# Current_Scaler.net
KiCad netlist of a schematic drawn in Altium Designer
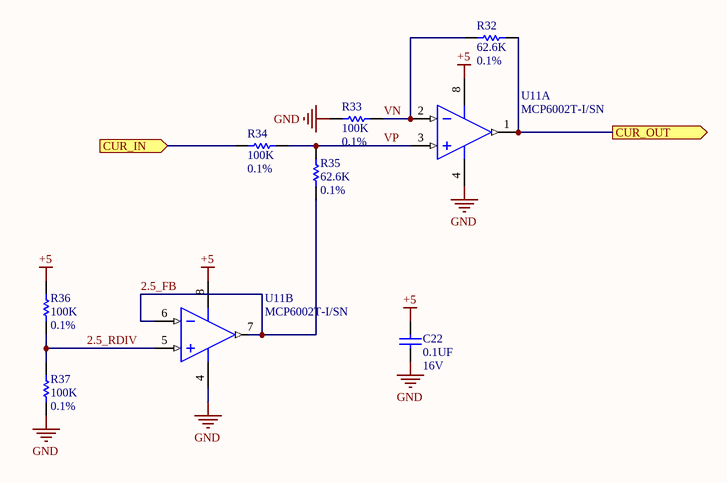
[diagram p0: Current Scaler.SchDoc]

(export (version "E")
  (design (tool "Eeschema 10.0.6"))
  (components
    (comp (ref "C22")
      (value "CAP 0603 0.1UF 16V 10% X7R")
      (footprint "0603_CAP")
      (description "Capacitor Surface Mount 0603 Footprint 0.1UF 16V 10% Tolerance Ceramic X7R")
      (fields
        (field (name "VAL") "0.1UF")
        (field (name "VOL") "16V")
        (field (name "MANUFACTURER") "Various")
        (field (name "VOLTAGE") "16V")
      )
      (libsource (lib "Passive Components") (part "cap"))
    )
    (comp (ref "R32")
      (value "RES 0603 62.6K 0.1%")
      (footprint "0603_RES")
      (description "Resistor Surface Mount, 51K Ohms, 0603 Footprint, 0.05% Tolerance 0.1W")
      (fields
        (field (name "VAL") "62.6K")
        (field (name "TOL") "0.1%")
        (field (name "MANUFACTURER") "Various")
        (field (name "TOLERANCE") "0.1%")
      )
      (libsource (lib "Passive Components") (part "res"))
    )
    (comp (ref "R33")
      (value "RES 0603 100K 0.1%")
      (footprint "0603_RES")
      (description "Resistor Surface Mount, 100K Ohms, 0603 Footprint, 0.1% Tolerance 0.1W")
      (fields
        (field (name "VAL") "100K")
        (field (name "TOL") "0.1%")
        (field (name "MANUFACTURER") "Various")
        (field (name "TOLERANCE") "0.1%")
      )
      (libsource (lib "Passive Components") (part "res"))
    )
    (comp (ref "R34")
      (value "RES 0603 100K 0.1%")
      (footprint "0603_RES")
      (description "Resistor Surface Mount, 100K Ohms, 0603 Footprint, 0.1% Tolerance 0.1W")
      (fields
        (field (name "VAL") "100K")
        (field (name "TOL") "0.1%")
        (field (name "MANUFACTURER") "Various")
        (field (name "TOLERANCE") "0.1%")
      )
      (libsource (lib "Passive Components") (part "res"))
    )
    (comp (ref "R35")
      (value "RES 0603 62.6K 0.1%")
      (footprint "0603_RES")
      (description "Resistor Surface Mount, 51K Ohms, 0603 Footprint, 0.05% Tolerance 0.1W")
      (fields
        (field (name "VAL") "62.6K")
        (field (name "TOL") "0.1%")
        (field (name "MANUFACTURER") "Various")
        (field (name "TOLERANCE") "0.1%")
      )
      (libsource (lib "Passive Components") (part "res"))
    )
    (comp (ref "R36")
      (value "RES 0603 100K 0.1%")
      (footprint "0603_RES")
      (description "Resistor Surface Mount, 100K Ohms, 0603 Footprint, 0.1% Tolerance 0.1W")
      (fields
        (field (name "VAL") "100K")
        (field (name "TOL") "0.1%")
        (field (name "MANUFACTURER") "Various")
        (field (name "TOLERANCE") "0.1%")
      )
      (libsource (lib "Passive Components") (part "res"))
    )
    (comp (ref "R37")
      (value "RES 0603 100K 0.1%")
      (footprint "0603_RES")
      (description "Resistor Surface Mount, 100K Ohms, 0603 Footprint, 0.1% Tolerance 0.1W")
      (fields
        (field (name "VAL") "100K")
        (field (name "TOL") "0.1%")
        (field (name "MANUFACTURER") "Various")
        (field (name "TOLERANCE") "0.1%")
      )
      (libsource (lib "Passive Components") (part "res"))
    )
    (comp (ref "U11")
      (value "MCP6002T-I/SN")
      (footprint "SOIC-SN8_L")
      (description "1 MHz, Low-Power Operational Amplifier, 8-Pin SOIC, Industrial Temperature, Tape and Reel")
      (libsource (lib "Altium Content Vault") (part "AMP-OPA-MCP6002-IL8"))
    )
  )
  (nets
    (net (code "1") (name "+5") (class "Default")
      (node (ref "C22") (pin "2") (pinfunction "2_2") (pintype "passive"))
      (node (ref "R36") (pin "2") (pinfunction "2_2") (pintype "passive"))
      (node (ref "U11") (pin "8") (pinfunction "VDD_8") (pintype "power_in"))
    )
    (net (code "2") (name "/2.5_FB") (class "Default")
      (node (ref "R35") (pin "1") (pinfunction "1_1") (pintype "passive"))
      (node (ref "U11") (pin "6") (pinfunction "VINB-_6") (pintype "input"))
      (node (ref "U11") (pin "7") (pinfunction "VOUTB_7") (pintype "output"))
    )
    (net (code "3") (name "/2.5_RDIV") (class "Default")
      (node (ref "R36") (pin "1") (pinfunction "1_1") (pintype "passive"))
      (node (ref "R37") (pin "2") (pinfunction "2_2") (pintype "passive"))
      (node (ref "U11") (pin "5") (pinfunction "VINB+_5") (pintype "input"))
    )
    (net (code "4") (name "/CUR_IN") (class "Default")
      (node (ref "R34") (pin "1") (pinfunction "1_1") (pintype "passive"))
    )
    (net (code "5") (name "/CUR_OUT") (class "Default")
      (node (ref "R32") (pin "1") (pinfunction "1_1") (pintype "passive"))
      (node (ref "U11") (pin "1") (pinfunction "VOUTA_1") (pintype "output"))
    )
    (net (code "6") (name "/VN") (class "Default")
      (node (ref "R32") (pin "2") (pinfunction "2_2") (pintype "passive"))
      (node (ref "R33") (pin "2") (pinfunction "2_2") (pintype "passive"))
      (node (ref "U11") (pin "2") (pinfunction "VINA-_2") (pintype "input"))
    )
    (net (code "7") (name "/VP") (class "Default")
      (node (ref "R34") (pin "2") (pinfunction "2_2") (pintype "passive"))
      (node (ref "R35") (pin "2") (pinfunction "2_2") (pintype "passive"))
      (node (ref "U11") (pin "3") (pinfunction "VINA+_3") (pintype "input"))
    )
    (net (code "8") (name "GND") (class "Default")
      (node (ref "C22") (pin "1") (pinfunction "1_1") (pintype "passive"))
      (node (ref "R33") (pin "1") (pinfunction "1_1") (pintype "passive"))
      (node (ref "R37") (pin "1") (pinfunction "1_1") (pintype "passive"))
      (node (ref "U11") (pin "4") (pinfunction "VSS_4") (pintype "power_in"))
    )
  )
)
